# TEFNUT_proto_v1.net
KiCad netlist of a schematic drawn in EAGLE
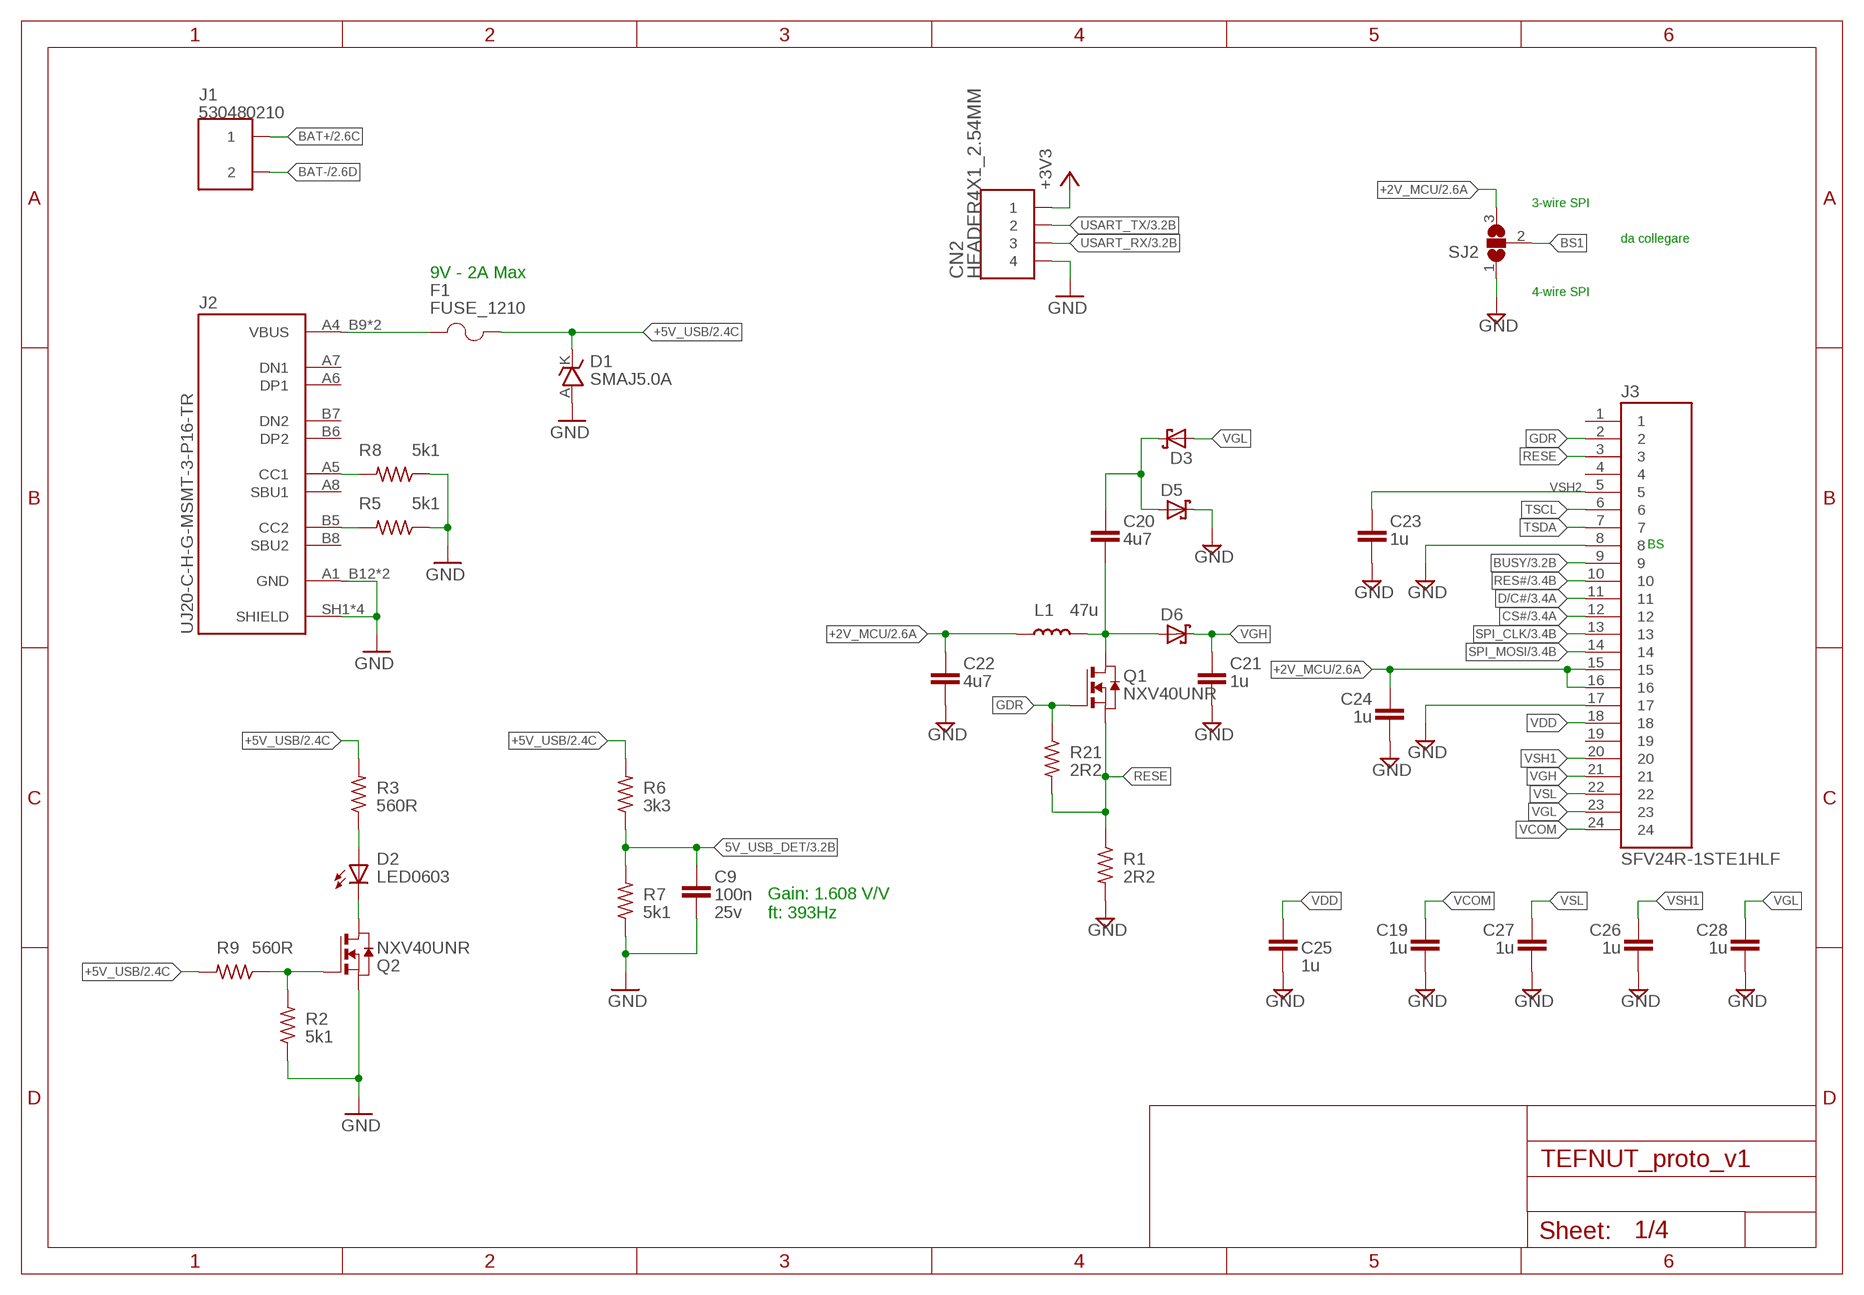
[diagram p0: schematic, sheet 1]
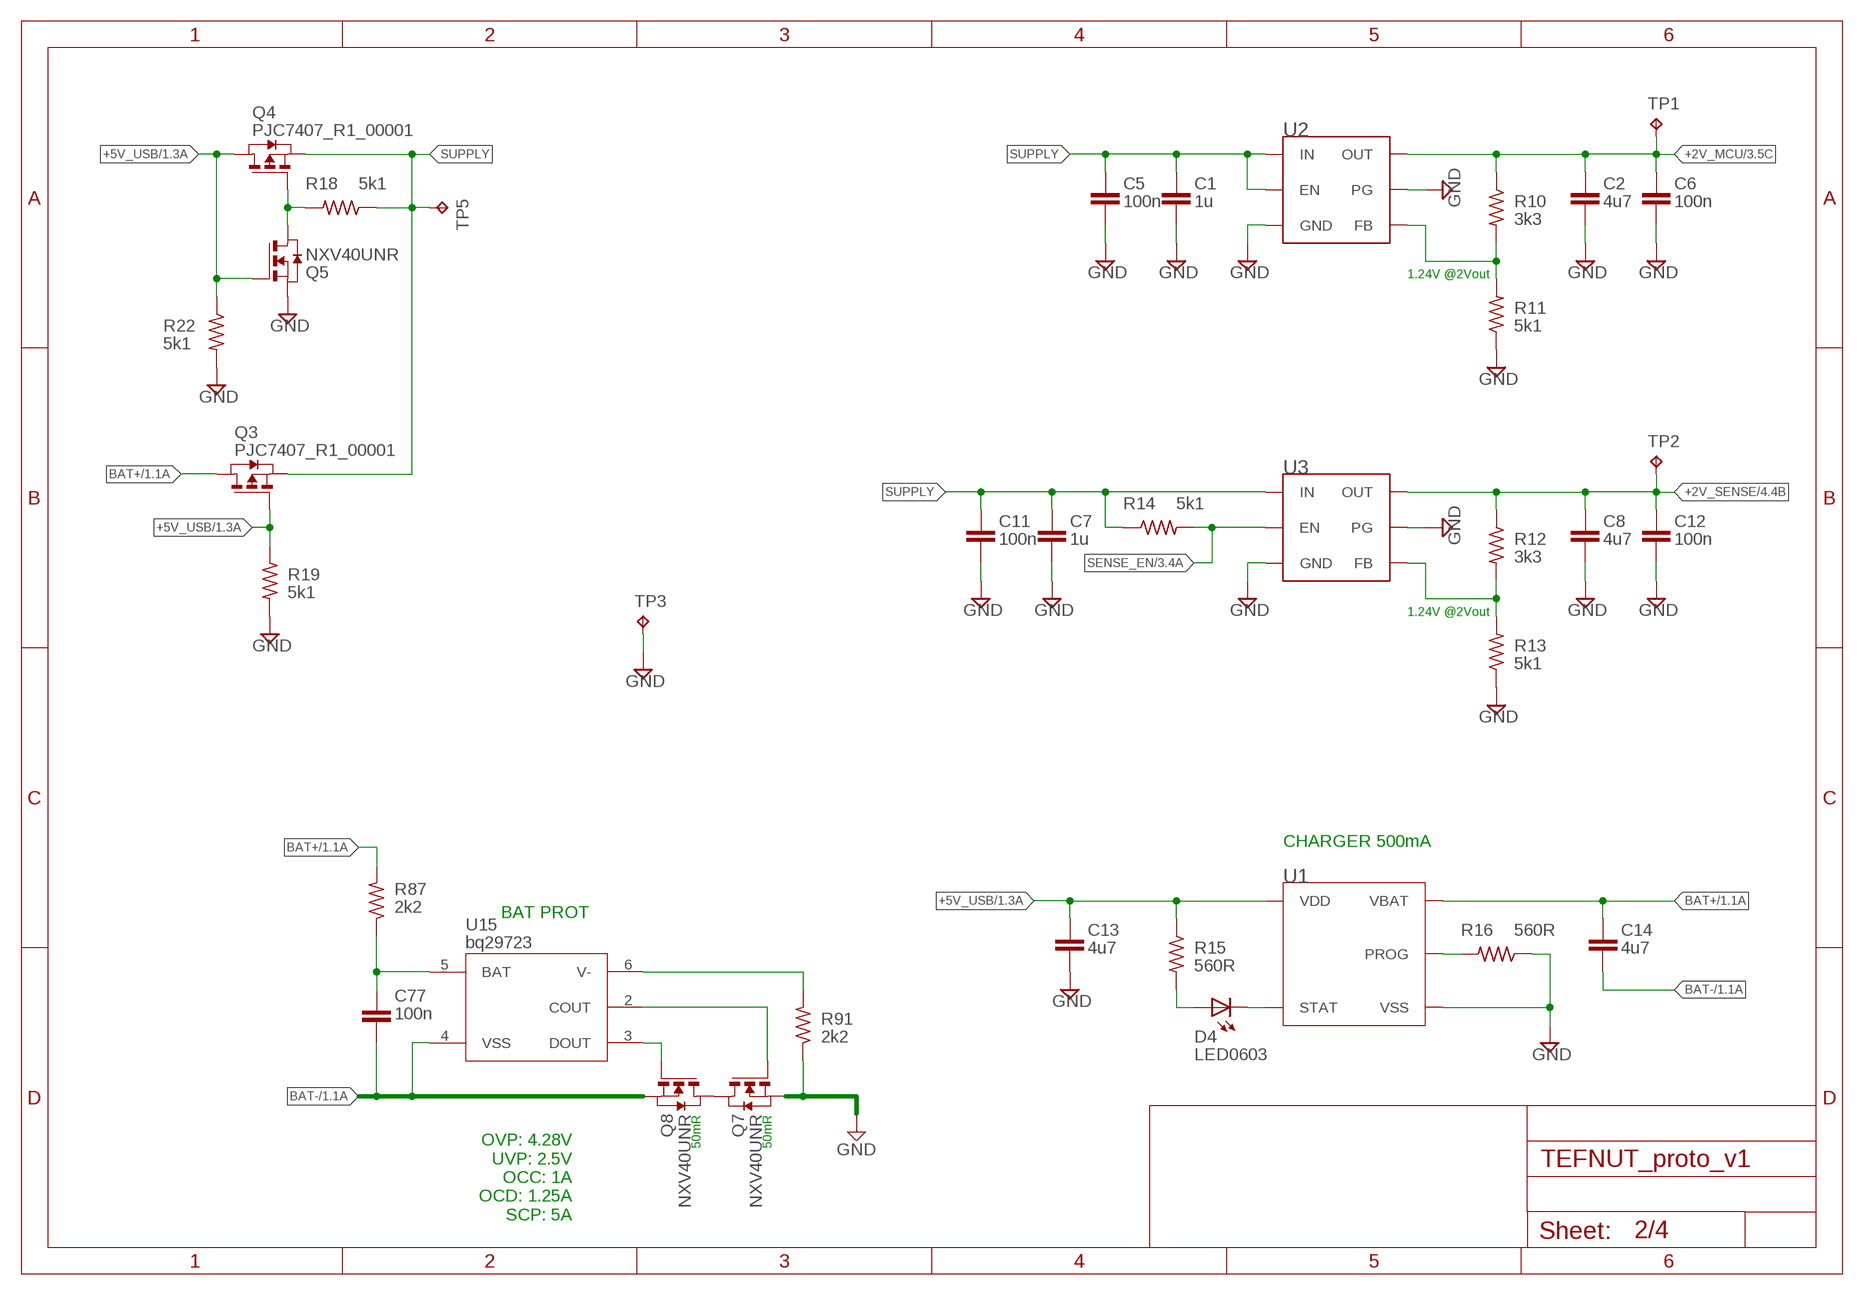
[diagram p1: schematic, sheet 2]
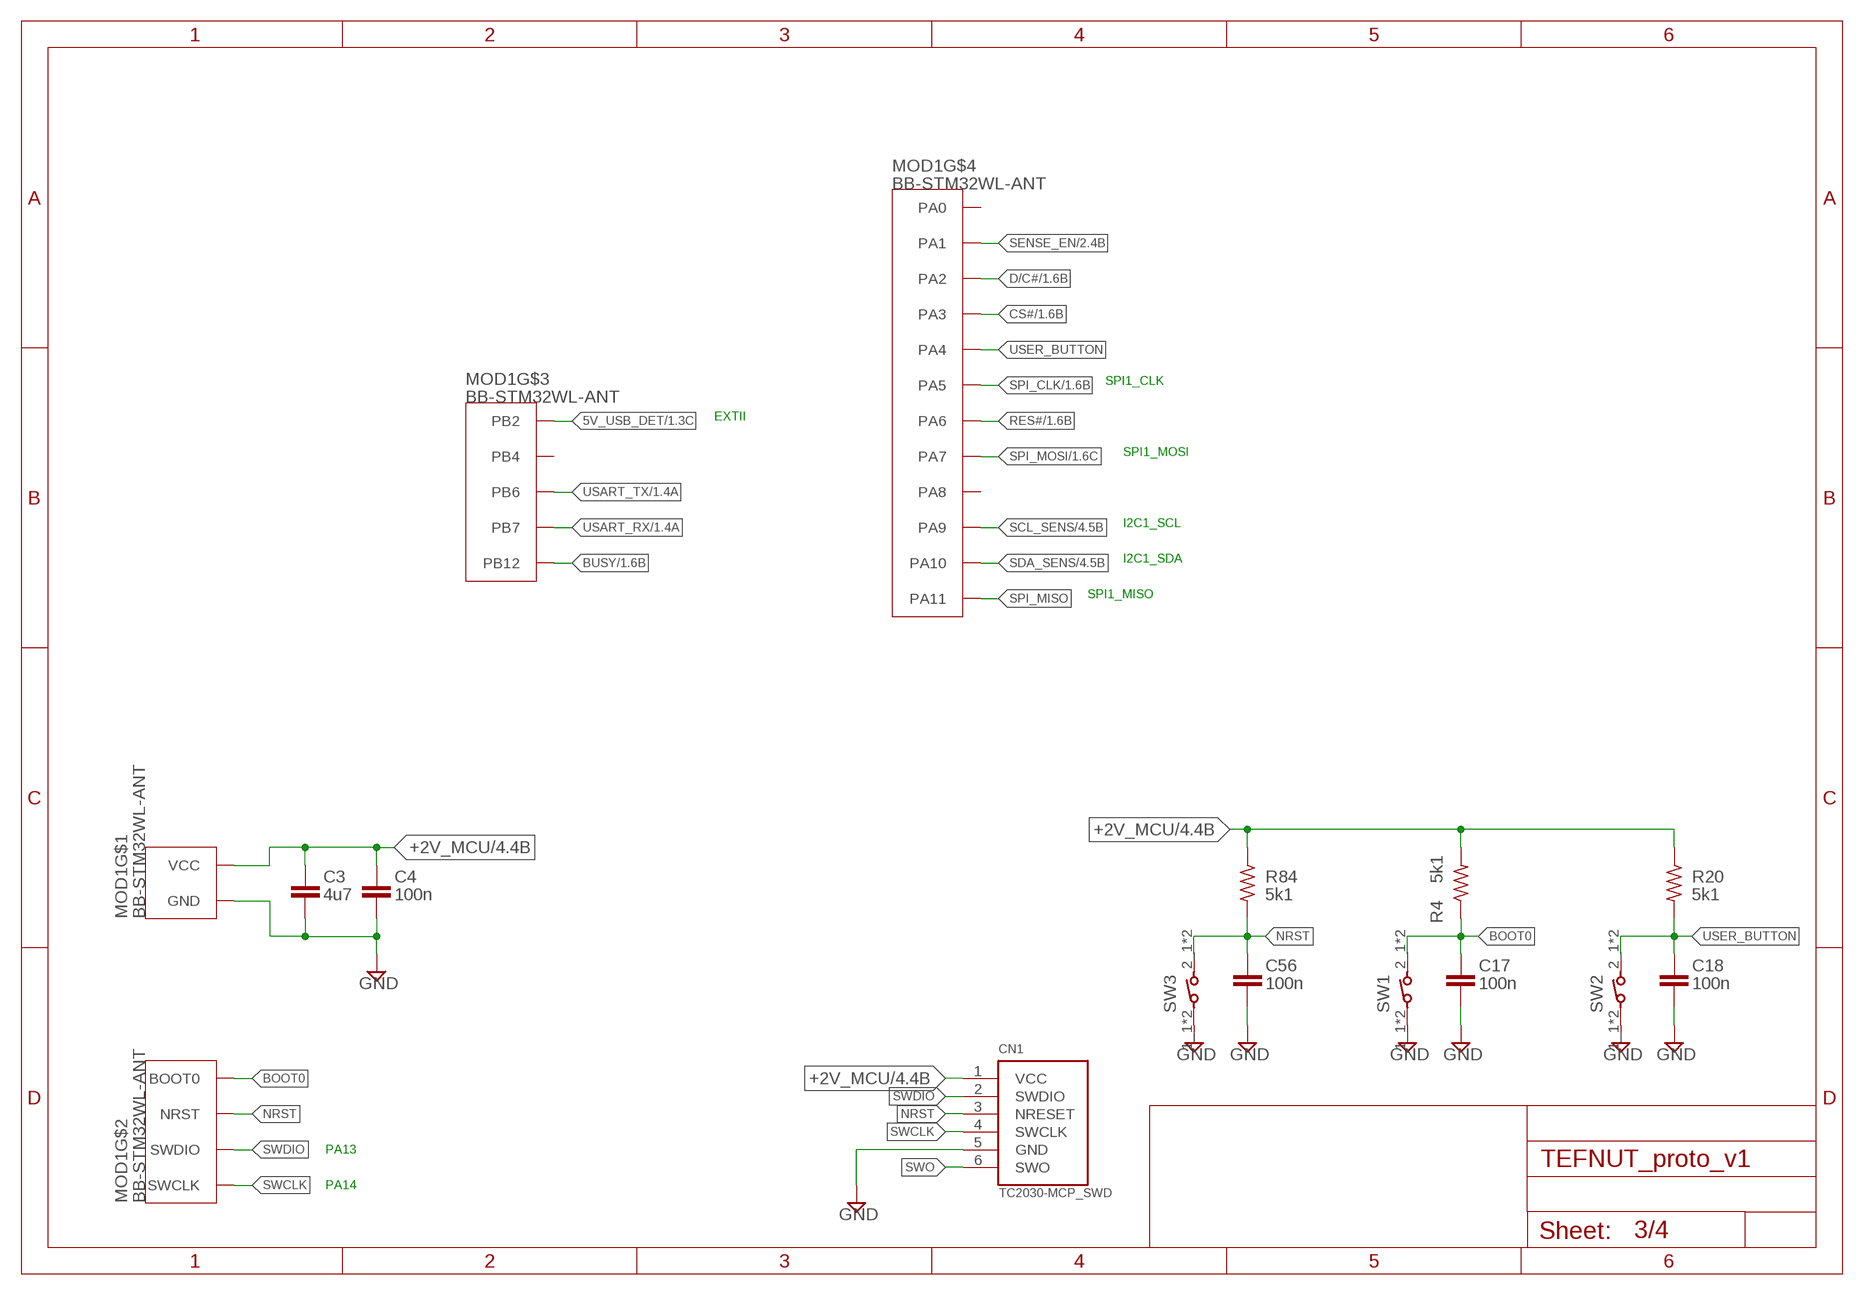
[diagram p2: schematic, sheet 3]
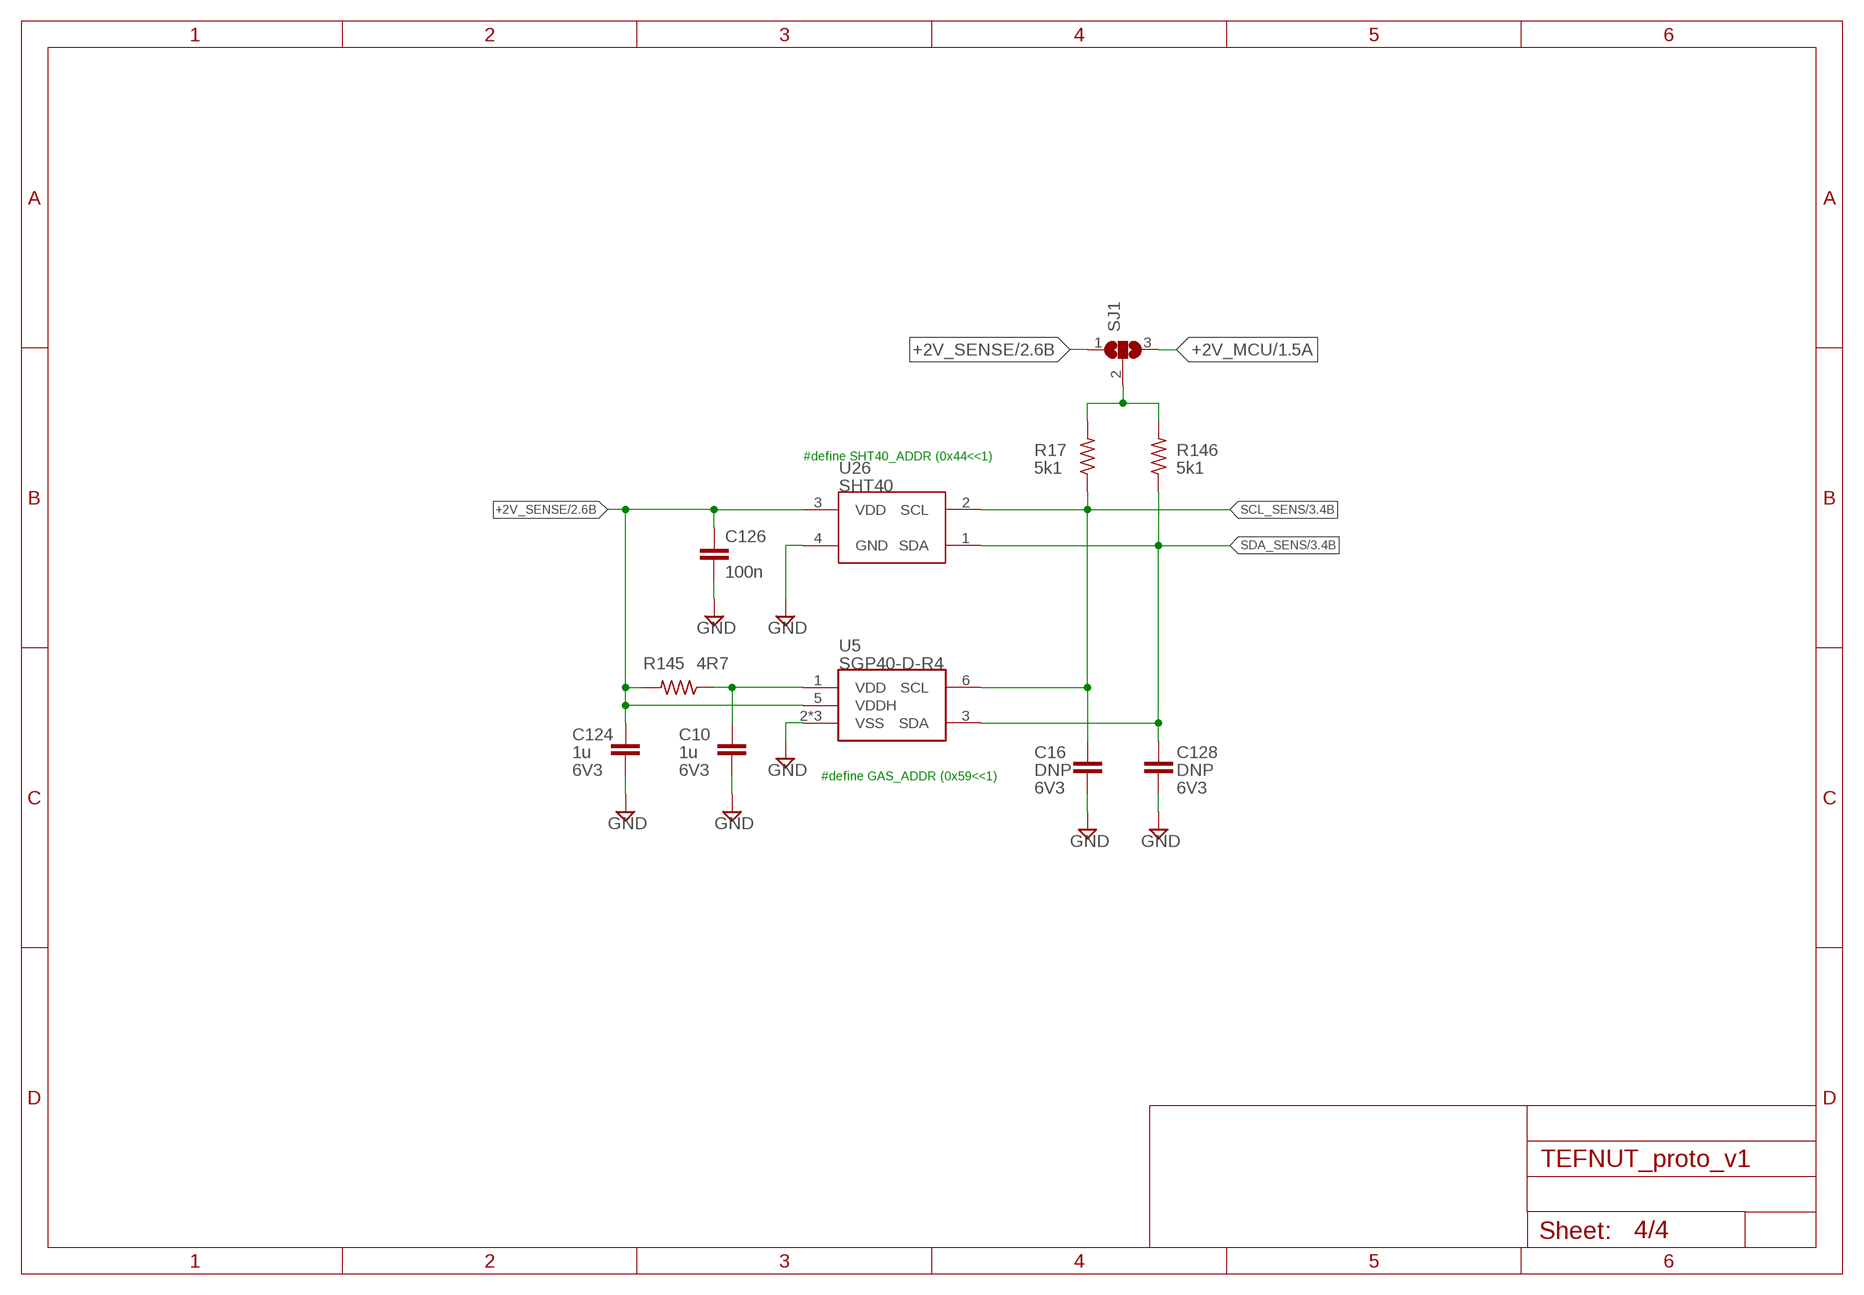
[diagram p3: schematic, sheet 4]

(export (version "E")
  (design (tool "Eeschema 10.0.6"))
  (components
    (comp (ref "C10")
      (value "1u")
      (footprint "eagle-import:C0603[1608]")
      (fields (field (name "PARTNO") "CL10A105KO8NNNC") (field (name "VOLT") "6V3"))
      (libsource (lib "eagle-import") (part "MP-PASS_vf.IZ1fKOIAQwecCdOCAm3Ehg_C0603"))
    )
    (comp (ref "C16")
      (value "DNP")
      (footprint "eagle-import:C0603[1608]")
      (fields (field (name "V") "6V3"))
      (libsource (lib "eagle-import") (part "C0603"))
    )
    (comp (ref "C124")
      (value "1u")
      (footprint "eagle-import:C0603[1608]")
      (fields (field (name "PARTNO") "CL10A105KO8NNNC") (field (name "VOLT") "6V3"))
      (libsource (lib "eagle-import") (part "MP-PASS_vf.IZ1fKOIAQwecCdOCAm3Ehg_C0603"))
    )
    (comp (ref "C126")
      (value "100n")
      (footprint "eagle-import:C0603[1608]")
      (fields (field (name "PARTNO") "CL10B104KO8NNNC"))
      (libsource (lib "eagle-import") (part "C0603"))
    )
    (comp (ref "C128")
      (value "DNP")
      (footprint "eagle-import:C0603[1608]")
      (fields (field (name "VOLT") "6V3"))
      (libsource (lib "eagle-import") (part "C0603"))
    )
    (comp (ref "R17")
      (value "5k1")
      (footprint "eagle-import:R0603[1608]")
      (fields (field (name "PARTNO") "RC0603FR-075K1L"))
      (libsource (lib "eagle-import") (part "R_0603"))
    )
    (comp (ref "R145")
      (value "4R7")
      (footprint "eagle-import:R0603")
      (fields (field (name "PARTNO") "AC0603FR-072R2L"))
      (libsource (lib "eagle-import") (part "MP-PASS_vf.IZ1fKOIAQwecCdOCAm3Ehg_R_0603"))
    )
    (comp (ref "R146")
      (value "5k1")
      (footprint "eagle-import:R0603[1608]")
      (fields (field (name "PARTNO") "RC0603FR-075K1L"))
      (libsource (lib "eagle-import") (part "R_0603"))
    )
    (comp (ref "SJ1")
      (value "SJ2W")
      (footprint "eagle-import:SJ_2")
      (libsource (lib "eagle-import") (part "SJ2W"))
    )
    (comp (ref "U5")
      (value "SGP40-D-R4")
      (footprint "eagle-import:DFN6")
      (fields (field (name "PARTNO") "SGP30-2.5K") (field (name "PARTNO_1") "SGP40-D-R4"))
      (libsource (lib "eagle-import") (part "SGP30"))
    )
    (comp (ref "U26")
      (value "SHT40")
      (footprint "eagle-import:SH4X")
      (fields (field (name "PARTNO") "SHT40-AD1B-R3"))
      (libsource (lib "eagle-import") (part "SHT40"))
    )
    (comp (ref "C3")
      (value "4u7")
      (footprint "eagle-import:C0805[2012]")
      (fields (field (name "PARTNO") "CL21A475KOFNNNE"))
      (libsource (lib "eagle-import") (part "MP-PASS_vf.IZ1fKOIAQwecCdOCAm3Ehg_C0805"))
    )
    (comp (ref "C4")
      (value "100n")
      (footprint "eagle-import:C0805[2012]")
      (fields (field (name "PARTNO") "CC0805KRX7R7BB104"))
      (libsource (lib "eagle-import") (part "MP-PASS_vf.IZ1fKOIAQwecCdOCAm3Ehg_C0805"))
    )
    (comp (ref "C17")
      (value "100n")
      (footprint "eagle-import:C0603[1608]")
      (fields (field (name "PARTNO") "CL10B104KO8NNNC"))
      (libsource (lib "eagle-import") (part "AlmaPASS_vf.OlGPyyHlR2mLU9oE-NbbHQ_C0603"))
    )
    (comp (ref "C18")
      (value "100n")
      (footprint "eagle-import:C0603[1608]")
      (fields (field (name "PARTNO") "CL10B104KO8NNNC"))
      (libsource (lib "eagle-import") (part "AlmaPASS_vf.OlGPyyHlR2mLU9oE-NbbHQ_C0603"))
    )
    (comp (ref "C56")
      (value "100n")
      (footprint "eagle-import:C0603[1608]")
      (fields (field (name "PARTNO") "CL10B104KO8NNNC"))
      (libsource (lib "eagle-import") (part "AlmaPASS_vf.OlGPyyHlR2mLU9oE-NbbHQ_C0603"))
    )
    (comp (ref "CN1")
      (value "TC2030-MCP_SWD")
      (footprint "eagle-import:TC2030-IDC")
      (libsource (lib "eagle-import") (part "TC2030-MCP_SWD"))
    )
    (comp (ref "MOD1")
      (value "BB-STM32WL-ANT")
      (footprint "eagle-import:BB-STM32WL-ANT")
      (libsource (lib "eagle-import") (part "BB-STM32WL-ANT"))
    )
    (comp (ref "R4")
      (value "5k1")
      (footprint "eagle-import:R0603")
      (fields (field (name "PARTNO") "RC0603FR-075K1L"))
      (libsource (lib "eagle-import") (part "MP-PASS_vf.IZ1fKOIAQwecCdOCAm3Ehg_R_0603"))
    )
    (comp (ref "R20")
      (value "5k1")
      (footprint "eagle-import:R0603")
      (fields (field (name "PARTNO") "RC0603FR-075K1L"))
      (libsource (lib "eagle-import") (part "MP-PASS_vf.IZ1fKOIAQwecCdOCAm3Ehg_R_0603"))
    )
    (comp (ref "R84")
      (value "5k1")
      (footprint "eagle-import:R0603")
      (fields (field (name "PARTNO") "RC0603FR-075K1L"))
      (libsource (lib "eagle-import") (part "MP-PASS_vf.IZ1fKOIAQwecCdOCAm3Ehg_R_0603"))
    )
    (comp (ref "SW1")
      (value "SWITCHEVQ_4PIN")
      (footprint "eagle-import:EVQ-P7L01P")
      (fields (field (name "PARTNO") "EVQP7L01P"))
      (libsource (lib "eagle-import") (part "SWITCHEVQ_4PIN"))
    )
    (comp (ref "SW2")
      (value "SWITCHEVQ_4PIN")
      (footprint "eagle-import:EVQ-P7L01P")
      (fields (field (name "PARTNO") "EVQP7L01P"))
      (libsource (lib "eagle-import") (part "SWITCHEVQ_4PIN"))
    )
    (comp (ref "SW3")
      (value "SWITCHEVQ_4PIN")
      (footprint "eagle-import:EVQ-P7L01P")
      (fields (field (name "PARTNO") "EVQP7L01P"))
      (libsource (lib "eagle-import") (part "SWITCHEVQ_4PIN"))
    )
    (comp (ref "C1")
      (value "1u")
      (footprint "eagle-import:C0603[1608]")
      (fields (field (name "PARTNO") "CL10A105KO8NNNC"))
      (libsource (lib "eagle-import") (part "MP-PASS_vf.IZ1fKOIAQwecCdOCAm3Ehg_C0603"))
    )
    (comp (ref "C2")
      (value "4u7")
      (footprint "eagle-import:C0603[1608]")
      (fields (field (name "PARTNO") "CL10A475KO8NNNC"))
      (libsource (lib "eagle-import") (part "MP-PASS_vf.IZ1fKOIAQwecCdOCAm3Ehg_C0603"))
    )
    (comp (ref "C5")
      (value "100n")
      (footprint "eagle-import:C0603[1608]")
      (fields (field (name "PARTNO") "CL10B104KO8NNNC"))
      (libsource (lib "eagle-import") (part "MP-PASS_vf.IZ1fKOIAQwecCdOCAm3Ehg_C0603"))
    )
    (comp (ref "C6")
      (value "100n")
      (footprint "eagle-import:C0603[1608]")
      (fields (field (name "PARTNO") "CL10B104KO8NNNC"))
      (libsource (lib "eagle-import") (part "MP-PASS_vf.IZ1fKOIAQwecCdOCAm3Ehg_C0603"))
    )
    (comp (ref "C7")
      (value "1u")
      (footprint "eagle-import:C0603[1608]")
      (fields (field (name "PARTNO") "CL10A105KO8NNNC"))
      (libsource (lib "eagle-import") (part "MP-PASS_vf.IZ1fKOIAQwecCdOCAm3Ehg_C0603"))
    )
    (comp (ref "C8")
      (value "4u7")
      (footprint "eagle-import:C0603[1608]")
      (fields (field (name "PARTNO") "CL10A475KO8NNNC"))
      (libsource (lib "eagle-import") (part "MP-PASS_vf.IZ1fKOIAQwecCdOCAm3Ehg_C0603"))
    )
    (comp (ref "C11")
      (value "100n")
      (footprint "eagle-import:C0603[1608]")
      (fields (field (name "PARTNO") "CL10B104KO8NNNC"))
      (libsource (lib "eagle-import") (part "MP-PASS_vf.IZ1fKOIAQwecCdOCAm3Ehg_C0603"))
    )
    (comp (ref "C12")
      (value "100n")
      (footprint "eagle-import:C0603[1608]")
      (fields (field (name "PARTNO") "CL10B104KO8NNNC"))
      (libsource (lib "eagle-import") (part "MP-PASS_vf.IZ1fKOIAQwecCdOCAm3Ehg_C0603"))
    )
    (comp (ref "C13")
      (value "4u7")
      (footprint "eagle-import:C0805[2012]")
      (fields (field (name "PARTNO") "CL21A475KOFNNNE"))
      (libsource (lib "eagle-import") (part "MP-PASS_vf.IZ1fKOIAQwecCdOCAm3Ehg_C0805"))
    )
    (comp (ref "C14")
      (value "4u7")
      (footprint "eagle-import:C0805[2012]")
      (fields (field (name "PARTNO") "CL21A475KOFNNNE"))
      (libsource (lib "eagle-import") (part "MP-PASS_vf.IZ1fKOIAQwecCdOCAm3Ehg_C0805"))
    )
    (comp (ref "C77")
      (value "100n")
      (footprint "eagle-import:C0603[1608]")
      (fields (field (name "PARTNO") "CL10B104KO8NNNC"))
      (libsource (lib "eagle-import") (part "MP-PASS_vf.IZ1fKOIAQwecCdOCAm3Ehg_C0603"))
    )
    (comp (ref "D4")
      (value "LED0603")
      (footprint "eagle-import:LED0603")
      (libsource (lib "eagle-import") (part "LED0603"))
    )
    (comp (ref "Q3")
      (value "PJC7407_R1_00001")
      (footprint "eagle-import:SOT323-3(SC-70-3)")
      (libsource (lib "eagle-import") (part "MOSFET_P_SOT323"))
    )
    (comp (ref "Q4")
      (value "PJC7407_R1_00001")
      (footprint "eagle-import:SOT323-3(SC-70-3)")
      (libsource (lib "eagle-import") (part "MOSFET_P_SOT323"))
    )
    (comp (ref "Q5")
      (value "NXV40UNR")
      (footprint "eagle-import:SOT23-3")
      (libsource (lib "eagle-import") (part "MOSFET_N_SOT23-3"))
    )
    (comp (ref "Q7")
      (value "NXV40UNR")
      (footprint "eagle-import:SOT23-3")
      (libsource (lib "eagle-import") (part "MOSFET_N_SOT23-3"))
    )
    (comp (ref "Q8")
      (value "NXV40UNR")
      (footprint "eagle-import:SOT23-3")
      (libsource (lib "eagle-import") (part "MOSFET_N_SOT23-3"))
    )
    (comp (ref "R10")
      (value "3k3")
      (footprint "eagle-import:R0603")
      (fields (field (name "PARTNO") "RC0603FR-073K3L"))
      (libsource (lib "eagle-import") (part "MP-PASS_vf.IZ1fKOIAQwecCdOCAm3Ehg_R_0603"))
    )
    (comp (ref "R11")
      (value "5k1")
      (footprint "eagle-import:R0603")
      (fields (field (name "PARTNO") "RC0603FR-075K1L"))
      (libsource (lib "eagle-import") (part "MP-PASS_vf.IZ1fKOIAQwecCdOCAm3Ehg_R_0603"))
    )
    (comp (ref "R12")
      (value "3k3")
      (footprint "eagle-import:R0603")
      (fields (field (name "PARTNO") "RC0603FR-073K3L"))
      (libsource (lib "eagle-import") (part "MP-PASS_vf.IZ1fKOIAQwecCdOCAm3Ehg_R_0603"))
    )
    (comp (ref "R13")
      (value "5k1")
      (footprint "eagle-import:R0603")
      (fields (field (name "PARTNO") "RC0603FR-075K1L"))
      (libsource (lib "eagle-import") (part "MP-PASS_vf.IZ1fKOIAQwecCdOCAm3Ehg_R_0603"))
    )
    (comp (ref "R14")
      (value "5k1")
      (footprint "eagle-import:R0603")
      (fields (field (name "PARTNO") "RC0603FR-075K1L"))
      (libsource (lib "eagle-import") (part "MP-PASS_vf.IZ1fKOIAQwecCdOCAm3Ehg_R_0603"))
    )
    (comp (ref "R15")
      (value "560R")
      (footprint "eagle-import:R0603")
      (fields (field (name "PARTNO") "RC0603FR-07560RL"))
      (libsource (lib "eagle-import") (part "MP-PASS_vf.IZ1fKOIAQwecCdOCAm3Ehg_R_0603"))
    )
    (comp (ref "R16")
      (value "560R")
      (footprint "eagle-import:R0603")
      (fields (field (name "PARTNO") "RC0603FR-07560RL"))
      (libsource (lib "eagle-import") (part "MP-PASS_vf.IZ1fKOIAQwecCdOCAm3Ehg_R_0603"))
    )
    (comp (ref "R18")
      (value "5k1")
      (footprint "eagle-import:R0603[1608]")
      (fields (field (name "PARTNO") "RC0603FR-075K1L"))
      (libsource (lib "eagle-import") (part "R_0603"))
    )
    (comp (ref "R19")
      (value "5k1")
      (footprint "eagle-import:R0603[1608]")
      (fields (field (name "PARTNO") "RC0603FR-075K1L"))
      (libsource (lib "eagle-import") (part "R_0603"))
    )
    (comp (ref "R22")
      (value "5k1")
      (footprint "eagle-import:R0603[1608]")
      (fields (field (name "PARTNO") "RC0603FR-075K1L"))
      (libsource (lib "eagle-import") (part "R_0603"))
    )
    (comp (ref "R87")
      (value "2k2")
      (footprint "eagle-import:R0603")
      (fields (field (name "PARTNO") "ERJ-3EKF2201V"))
      (libsource (lib "eagle-import") (part "MP-PASS_vf.IZ1fKOIAQwecCdOCAm3Ehg_R_0603"))
    )
    (comp (ref "R91")
      (value "2k2")
      (footprint "eagle-import:R0603")
      (fields (field (name "PARTNO") "ERJ-3EKF2201V"))
      (libsource (lib "eagle-import") (part "MP-PASS_vf.IZ1fKOIAQwecCdOCAm3Ehg_R_0603"))
    )
    (comp (ref "TP1")
      (value "TPB1,27")
      (footprint "eagle-import:B1,27")
      (libsource (lib "eagle-import") (part "TPB1,27"))
    )
    (comp (ref "TP2")
      (value "TPB1,27")
      (footprint "eagle-import:B1,27")
      (libsource (lib "eagle-import") (part "TPB1,27"))
    )
    (comp (ref "TP3")
      (value "TPB1,27")
      (footprint "eagle-import:B1,27")
      (libsource (lib "eagle-import") (part "TPB1,27"))
    )
    (comp (ref "TP5")
      (value "TPB1,27")
      (footprint "eagle-import:B1,27")
      (libsource (lib "eagle-import") (part "TPB1,27"))
    )
    (comp (ref "U1")
      (value "MCP73831T")
      (footprint "eagle-import:SOT23-5")
      (fields (field (name "PARTNO") "MCP73831T-2DCI/OT"))
      (libsource (lib "eagle-import") (part "MCP73831T"))
    )
    (comp (ref "U2")
      (value "TPS7A2501DRVRDRV0006A-IPC_B")
      (footprint "eagle-import:6-WDFN")
      (fields
        (field (name "MANUFACTURER_PART_NUMBER") "TPS7A2501DRVR")
        (field (name "COPYRIGHT") "Copyright (C) 2025 Ultra Librarian. All rights reserved.")
      )
      (libsource (lib "eagle-import") (part "TPS7A2501DRVRDRV0006A-IPC_B"))
    )
    (comp (ref "U3")
      (value "TPS7A2501DRVRDRV0006A-IPC_B")
      (footprint "eagle-import:6-WDFN")
      (fields
        (field (name "MANUFACTURER_PART_NUMBER") "TPS7A2501DRVR")
        (field (name "COPYRIGHT") "Copyright (C) 2025 Ultra Librarian. All rights reserved.")
      )
      (libsource (lib "eagle-import") (part "TPS7A2501DRVRDRV0006A-IPC_B"))
    )
    (comp (ref "U15")
      (value "bq29723")
      (footprint "eagle-import:WSON6")
      (fields (field (name "PARTNO") "BQ29704DSER"))
      (libsource (lib "eagle-import") (part "BQ297XX"))
    )
    (comp (ref "C9")
      (value "100n")
      (footprint "eagle-import:C0603[1608]")
      (fields (field (name "PARTNO") "CL10B104KO8NNNC") (field (name "VOLT") "25v"))
      (libsource (lib "eagle-import") (part "MP-PASS_vf.IZ1fKOIAQwecCdOCAm3Ehg_C0603"))
    )
    (comp (ref "C19")
      (value "1u")
      (footprint "eagle-import:C0603[1608]")
      (fields (field (name "PARTNO") "CL10A105KO8NNNC"))
      (libsource (lib "eagle-import") (part "MP-PASS_vf.IZ1fKOIAQwecCdOCAm3Ehg_C0603"))
    )
    (comp (ref "C20")
      (value "4u7")
      (footprint "eagle-import:C0603[1608]")
      (fields (field (name "PARTNO") "CL10A475KO8NNNC"))
      (libsource (lib "eagle-import") (part "MP-PASS_vf.IZ1fKOIAQwecCdOCAm3Ehg_C0603"))
    )
    (comp (ref "C21")
      (value "1u")
      (footprint "eagle-import:C0603[1608]")
      (fields (field (name "PARTNO") "CL10A105KO8NNNC"))
      (libsource (lib "eagle-import") (part "MP-PASS_vf.IZ1fKOIAQwecCdOCAm3Ehg_C0603"))
    )
    (comp (ref "C22")
      (value "4u7")
      (footprint "eagle-import:C0603[1608]")
      (fields (field (name "PARTNO") "CL10A475KO8NNNC"))
      (libsource (lib "eagle-import") (part "MP-PASS_vf.IZ1fKOIAQwecCdOCAm3Ehg_C0603"))
    )
    (comp (ref "C23")
      (value "1u")
      (footprint "eagle-import:C0603[1608]")
      (fields (field (name "PARTNO") "CL10A105KO8NNNC"))
      (libsource (lib "eagle-import") (part "MP-PASS_vf.IZ1fKOIAQwecCdOCAm3Ehg_C0603"))
    )
    (comp (ref "C24")
      (value "1u")
      (footprint "eagle-import:C0603[1608]")
      (fields (field (name "PARTNO") "CL10A105KO8NNNC"))
      (libsource (lib "eagle-import") (part "MP-PASS_vf.IZ1fKOIAQwecCdOCAm3Ehg_C0603"))
    )
    (comp (ref "C25")
      (value "1u")
      (footprint "eagle-import:C0603[1608]")
      (fields (field (name "PARTNO") "CL10A105KO8NNNC"))
      (libsource (lib "eagle-import") (part "MP-PASS_vf.IZ1fKOIAQwecCdOCAm3Ehg_C0603"))
    )
    (comp (ref "C26")
      (value "1u")
      (footprint "eagle-import:C0603[1608]")
      (fields (field (name "PARTNO") "CL10A105KO8NNNC"))
      (libsource (lib "eagle-import") (part "MP-PASS_vf.IZ1fKOIAQwecCdOCAm3Ehg_C0603"))
    )
    (comp (ref "C27")
      (value "1u")
      (footprint "eagle-import:C0603[1608]")
      (fields (field (name "PARTNO") "CL10A105KO8NNNC"))
      (libsource (lib "eagle-import") (part "MP-PASS_vf.IZ1fKOIAQwecCdOCAm3Ehg_C0603"))
    )
    (comp (ref "C28")
      (value "1u")
      (footprint "eagle-import:C0603[1608]")
      (fields (field (name "PARTNO") "CL10A105KO8NNNC"))
      (libsource (lib "eagle-import") (part "MP-PASS_vf.IZ1fKOIAQwecCdOCAm3Ehg_C0603"))
    )
    (comp (ref "CN2")
      (value "HEADER4X1_2.54MM")
      (footprint "eagle-import:HEADER4X1_2.54MM")
      (libsource (lib "eagle-import") (part "HEADER4X1_2.54MM"))
    )
    (comp (ref "D1")
      (value "TVS214AC")
      (footprint "eagle-import:DO-214AC")
      (fields (field (name "PARTNO") "SMAJ5.0A"))
      (libsource (lib "eagle-import") (part "TVS214AC"))
    )
    (comp (ref "D2")
      (value "LED0603")
      (footprint "eagle-import:LED0603")
      (libsource (lib "eagle-import") (part "LED0603"))
    )
    (comp (ref "D3")
      (value "SCHOTTKY_DIODE_SOD123")
      (footprint "eagle-import:SOD123")
      (fields (field (name "PARTNO") "MBR0530"))
      (libsource (lib "eagle-import") (part "SCHOTTKY_DIODE_SOD123"))
    )
    (comp (ref "D5")
      (value "SCHOTTKY_DIODE_SOD123")
      (footprint "eagle-import:SOD123")
      (fields (field (name "PARTNO") "MBR0530"))
      (libsource (lib "eagle-import") (part "SCHOTTKY_DIODE_SOD123"))
    )
    (comp (ref "D6")
      (value "SCHOTTKY_DIODE_SOD123")
      (footprint "eagle-import:SOD123")
      (fields (field (name "PARTNO") "MBR0530"))
      (libsource (lib "eagle-import") (part "SCHOTTKY_DIODE_SOD123"))
    )
    (comp (ref "F1")
      (value "FUSE_1210")
      (footprint "eagle-import:R1210[3225]")
      (fields (field (name "PARTNO") "SMD1210B110TF/16"))
      (libsource (lib "eagle-import") (part "FUSE_1210"))
    )
    (comp (ref "J1")
      (value "530480210")
      (footprint "eagle-import:530480210")
      (libsource (lib "eagle-import") (part "530480210"))
    )
    (comp (ref "J2")
      (value "UJ20-C-H-G-MSMT-3-P16-TR")
      (footprint "eagle-import:SAMESKY_UJ20-C-H-G-MSMT-3-P16-TR")
      (fields (field (name "MANUFACTURER") "Same Sky") (field (name "PARTNO") "UJ20-C-H-G-MSMT-3-P16"))
      (libsource (lib "eagle-import") (part "UJ20-C-H-G-MSMT-3-P16-TR"))
    )
    (comp (ref "J3")
      (value "SFV24R-1STE1HLF")
      (footprint "eagle-import:AMPHENOL_SFV24R-1STE1HLF")
      (fields (field (name "MANUFACTURER") "Amphenol"))
      (libsource (lib "eagle-import") (part "SFV24R-1STE1HLF"))
    )
    (comp (ref "L1")
      (value "47u")
      (footprint "eagle-import:L0805[2012]")
      (fields (field (name "PARTNO") "MLF2012E100JT000"))
      (libsource (lib "eagle-import") (part "L0805"))
    )
    (comp (ref "Q1")
      (value "NXV40UNR")
      (footprint "eagle-import:SOT23-3")
      (libsource (lib "eagle-import") (part "MOSFET_N_SOT23-3"))
    )
    (comp (ref "Q2")
      (value "NXV40UNR")
      (footprint "eagle-import:SOT23-3")
      (libsource (lib "eagle-import") (part "MOSFET_N_SOT23-3"))
    )
    (comp (ref "R1")
      (value "2R2")
      (footprint "eagle-import:R0603")
      (fields (field (name "PARTNO") "ERJ-U03F2R20V"))
      (libsource (lib "eagle-import") (part "MP-PASS_vf.IZ1fKOIAQwecCdOCAm3Ehg_R_0603"))
    )
    (comp (ref "R2")
      (value "5k1")
      (footprint "eagle-import:R0603")
      (fields (field (name "PARTNO") "RC0603FR-075K1L"))
      (libsource (lib "eagle-import") (part "MP-PASS_vf.IZ1fKOIAQwecCdOCAm3Ehg_R_0603"))
    )
    (comp (ref "R3")
      (value "560R")
      (footprint "eagle-import:R0603")
      (fields (field (name "PARTNO") "RC0603FR-07560RL"))
      (libsource (lib "eagle-import") (part "MP-PASS_vf.IZ1fKOIAQwecCdOCAm3Ehg_R_0603"))
    )
    (comp (ref "R5")
      (value "5k1")
      (footprint "eagle-import:R0603")
      (fields (field (name "PARTNO") "RC0603FR-075K1L"))
      (libsource (lib "eagle-import") (part "MP-PASS_vf.IZ1fKOIAQwecCdOCAm3Ehg_R_0603"))
    )
    (comp (ref "R6")
      (value "3k3")
      (footprint "eagle-import:R0603")
      (fields (field (name "PARTNO") "RC0603FR-073K3L"))
      (libsource (lib "eagle-import") (part "MP-PASS_vf.IZ1fKOIAQwecCdOCAm3Ehg_R_0603"))
    )
    (comp (ref "R7")
      (value "5k1")
      (footprint "eagle-import:R0603")
      (fields (field (name "PARTNO") "RC0603FR-075K1L"))
      (libsource (lib "eagle-import") (part "MP-PASS_vf.IZ1fKOIAQwecCdOCAm3Ehg_R_0603"))
    )
    (comp (ref "R8")
      (value "5k1")
      (footprint "eagle-import:R0603")
      (fields (field (name "PARTNO") "RC0603FR-075K1L"))
      (libsource (lib "eagle-import") (part "MP-PASS_vf.IZ1fKOIAQwecCdOCAm3Ehg_R_0603"))
    )
    (comp (ref "R9")
      (value "560R")
      (footprint "eagle-import:R0603")
      (fields (field (name "PARTNO") "RC0603FR-07560RL"))
      (libsource (lib "eagle-import") (part "MP-PASS_vf.IZ1fKOIAQwecCdOCAm3Ehg_R_0603"))
    )
    (comp (ref "R21")
      (value "2R2")
      (footprint "eagle-import:R0603")
      (fields (field (name "PARTNO") "ERJ-U03F2R20V"))
      (libsource (lib "eagle-import") (part "MP-PASS_vf.IZ1fKOIAQwecCdOCAm3Ehg_R_0603"))
    )
    (comp (ref "SJ2")
      (value "SJ2W")
      (footprint "eagle-import:SJ_2")
      (libsource (lib "eagle-import") (part "SJ2W"))
    )
  )
  (nets
    (net (code "1") (name "+2V_MCU") (class "Default")
      (node (ref "C2") (pin "1") (pinfunction "1_1") (pintype "passive"))
      (node (ref "C22") (pin "1") (pinfunction "1_1") (pintype "passive"))
      (node (ref "C24") (pin "1") (pinfunction "1_1") (pintype "passive"))
      (node (ref "C3") (pin "1") (pinfunction "1_1") (pintype "passive"))
      (node (ref "C4") (pin "1") (pinfunction "1_1") (pintype "passive"))
      (node (ref "C6") (pin "1") (pinfunction "1_1") (pintype "passive"))
      (node (ref "CN1") (pin "1") (pinfunction "VCC_1") (pintype "bidirectional"))
      (node (ref "J3") (pin "15") (pinfunction "15_15") (pintype "passive"))
      (node (ref "J3") (pin "16") (pinfunction "16_16") (pintype "passive"))
      (node (ref "L1") (pin "1") (pinfunction "1_1") (pintype "passive"))
      (node (ref "MOD1") (pin "VCC") (pinfunction "VCC_VCC") (pintype "bidirectional"))
      (node (ref "R10") (pin "1") (pinfunction "1_1") (pintype "passive"))
      (node (ref "R20") (pin "1") (pinfunction "1_1") (pintype "passive"))
      (node (ref "R4") (pin "2") (pinfunction "2_2") (pintype "passive"))
      (node (ref "R84") (pin "1") (pinfunction "1_1") (pintype "passive"))
      (node (ref "SJ1") (pin "3") (pinfunction "3_3") (pintype "passive"))
      (node (ref "SJ2") (pin "3") (pinfunction "3_3") (pintype "passive"))
      (node (ref "TP1") (pin "TP") (pinfunction "TP_TP") (pintype "input"))
      (node (ref "U2") (pin "1") (pinfunction "OUT_1") (pintype "power_in"))
    )
    (net (code "2") (name "+2V_SENSE") (class "Default")
      (node (ref "C12") (pin "1") (pinfunction "1_1") (pintype "passive"))
      (node (ref "C124") (pin "2") (pinfunction "2_2") (pintype "passive"))
      (node (ref "C126") (pin "1") (pinfunction "1_1") (pintype "passive"))
      (node (ref "C8") (pin "1") (pinfunction "1_1") (pintype "passive"))
      (node (ref "R12") (pin "1") (pinfunction "1_1") (pintype "passive"))
      (node (ref "R145") (pin "2") (pinfunction "2_2") (pintype "passive"))
      (node (ref "SJ1") (pin "1") (pinfunction "1_1") (pintype "passive"))
      (node (ref "TP2") (pin "TP") (pinfunction "TP_TP") (pintype "input"))
      (node (ref "U26") (pin "3") (pinfunction "VDD_3") (pintype "bidirectional"))
      (node (ref "U3") (pin "1") (pinfunction "OUT_1") (pintype "power_in"))
      (node (ref "U5") (pin "5") (pinfunction "VDDH_5") (pintype "bidirectional"))
    )
    (net (code "3") (name "+3V3") (class "Default")
      (node (ref "CN2") (pin "1") (pinfunction "1_1") (pintype "bidirectional"))
    )
    (net (code "4") (name "+5V_USB") (class "Default")
      (node (ref "C13") (pin "1") (pinfunction "1_1") (pintype "passive"))
      (node (ref "D1") (pin "K") (pinfunction "K_K") (pintype "bidirectional"))
      (node (ref "F1") (pin "2") (pinfunction "2_2") (pintype "bidirectional"))
      (node (ref "Q3") (pin "1") (pinfunction "G_1") (pintype "passive"))
      (node (ref "Q4") (pin "3") (pinfunction "D_3") (pintype "passive"))
      (node (ref "Q5") (pin "1") (pinfunction "G_1") (pintype "passive"))
      (node (ref "R15") (pin "1") (pinfunction "1_1") (pintype "passive"))
      (node (ref "R19") (pin "1") (pinfunction "1_1") (pintype "passive"))
      (node (ref "R22") (pin "1") (pinfunction "1_1") (pintype "passive"))
      (node (ref "R3") (pin "2") (pinfunction "2_2") (pintype "passive"))
      (node (ref "R6") (pin "2") (pinfunction "2_2") (pintype "passive"))
      (node (ref "R9") (pin "2") (pinfunction "2_2") (pintype "passive"))
      (node (ref "U1") (pin "4") (pinfunction "VDD_4") (pintype "passive"))
    )
    (net (code "5") (name "5V_USB_DET") (class "Default")
      (node (ref "C9") (pin "1") (pinfunction "1_1") (pintype "passive"))
      (node (ref "MOD1") (pin "PB2") (pinfunction "PB2_PB2") (pintype "bidirectional"))
      (node (ref "R6") (pin "1") (pinfunction "1_1") (pintype "passive"))
      (node (ref "R7") (pin "2") (pinfunction "2_2") (pintype "passive"))
    )
    (net (code "6") (name "BAT+") (class "Default")
      (node (ref "C14") (pin "1") (pinfunction "1_1") (pintype "passive"))
      (node (ref "J1") (pin "1") (pinfunction "1_1") (pintype "bidirectional"))
      (node (ref "Q3") (pin "3") (pinfunction "D_3") (pintype "passive"))
      (node (ref "R87") (pin "2") (pinfunction "2_2") (pintype "passive"))
      (node (ref "U1") (pin "3") (pinfunction "VBAT_3") (pintype "passive"))
    )
    (net (code "7") (name "BAT-") (class "Default")
      (node (ref "C14") (pin "2") (pinfunction "2_2") (pintype "passive"))
      (node (ref "C77") (pin "2") (pinfunction "2_2") (pintype "passive"))
      (node (ref "J1") (pin "2") (pinfunction "2_2") (pintype "bidirectional"))
      (node (ref "Q8") (pin "2") (pinfunction "S_2") (pintype "passive"))
      (node (ref "U15") (pin "4") (pinfunction "VSS_4") (pintype "bidirectional"))
    )
    (net (code "8") (name "BOOT0") (class "Default")
      (node (ref "C17") (pin "1") (pinfunction "1_1") (pintype "passive"))
      (node (ref "MOD1") (pin "BOOT0") (pinfunction "BOOT0_BOOT0") (pintype "bidirectional"))
      (node (ref "R4") (pin "1") (pinfunction "1_1") (pintype "passive"))
      (node (ref "SW1") (pin "2_1") (pinfunction "2_2_1") (pintype "passive"))
      (node (ref "SW1") (pin "2_2") (pinfunction "2_2_2") (pintype "passive"))
    )
    (net (code "9") (name "BS1") (class "Default")
      (node (ref "SJ2") (pin "2") (pinfunction "2_2") (pintype "passive"))
    )
    (net (code "10") (name "BUSY") (class "Default")
      (node (ref "J3") (pin "9") (pinfunction "9_9") (pintype "passive"))
      (node (ref "MOD1") (pin "PB12") (pinfunction "PB12_PB12") (pintype "bidirectional"))
    )
    (net (code "11") (name "CS#") (class "Default")
      (node (ref "J3") (pin "12") (pinfunction "12_12") (pintype "passive"))
      (node (ref "MOD1") (pin "PA3") (pinfunction "PA3_PA3") (pintype "bidirectional"))
    )
    (net (code "12") (name "D{slash}C#") (class "Default")
      (node (ref "J3") (pin "11") (pinfunction "11_11") (pintype "passive"))
      (node (ref "MOD1") (pin "PA2") (pinfunction "PA2_PA2") (pintype "bidirectional"))
    )
    (net (code "13") (name "GDR") (class "Default")
      (node (ref "J3") (pin "2") (pinfunction "2_2") (pintype "passive"))
      (node (ref "Q1") (pin "1") (pinfunction "G_1") (pintype "passive"))
      (node (ref "R21") (pin "1") (pinfunction "1_1") (pintype "passive"))
    )
    (net (code "14") (name "GND") (class "Default")
      (node (ref "C1") (pin "2") (pinfunction "2_2") (pintype "passive"))
      (node (ref "C10") (pin "1") (pinfunction "1_1") (pintype "passive"))
      (node (ref "C11") (pin "2") (pinfunction "2_2") (pintype "passive"))
      (node (ref "C12") (pin "2") (pinfunction "2_2") (pintype "passive"))
      (node (ref "C124") (pin "1") (pinfunction "1_1") (pintype "passive"))
      (node (ref "C126") (pin "2") (pinfunction "2_2") (pintype "passive"))
      (node (ref "C128") (pin "1") (pinfunction "1_1") (pintype "passive"))
      (node (ref "C13") (pin "2") (pinfunction "2_2") (pintype "passive"))
      (node (ref "C16") (pin "1") (pinfunction "1_1") (pintype "passive"))
      (node (ref "C17") (pin "2") (pinfunction "2_2") (pintype "passive"))
      (node (ref "C18") (pin "2") (pinfunction "2_2") (pintype "passive"))
      (node (ref "C19") (pin "2") (pinfunction "2_2") (pintype "passive"))
      (node (ref "C2") (pin "2") (pinfunction "2_2") (pintype "passive"))
      (node (ref "C21") (pin "2") (pinfunction "2_2") (pintype "passive"))
      (node (ref "C22") (pin "2") (pinfunction "2_2") (pintype "passive"))
      (node (ref "C23") (pin "2") (pinfunction "2_2") (pintype "passive"))
      (node (ref "C24") (pin "2") (pinfunction "2_2") (pintype "passive"))
      (node (ref "C25") (pin "2") (pinfunction "2_2") (pintype "passive"))
      (node (ref "C26") (pin "2") (pinfunction "2_2") (pintype "passive"))
      (node (ref "C27") (pin "2") (pinfunction "2_2") (pintype "passive"))
      (node (ref "C28") (pin "2") (pinfunction "2_2") (pintype "passive"))
      (node (ref "C3") (pin "2") (pinfunction "2_2") (pintype "passive"))
      (node (ref "C4") (pin "2") (pinfunction "2_2") (pintype "passive"))
      (node (ref "C5") (pin "2") (pinfunction "2_2") (pintype "passive"))
      (node (ref "C56") (pin "2") (pinfunction "2_2") (pintype "passive"))
      (node (ref "C6") (pin "2") (pinfunction "2_2") (pintype "passive"))
      (node (ref "C7") (pin "2") (pinfunction "2_2") (pintype "passive"))
      (node (ref "C8") (pin "2") (pinfunction "2_2") (pintype "passive"))
      (node (ref "C9") (pin "2") (pinfunction "2_2") (pintype "passive"))
      (node (ref "CN1") (pin "5") (pinfunction "GND_5") (pintype "bidirectional"))
      (node (ref "CN2") (pin "4") (pinfunction "4_4") (pintype "bidirectional"))
      (node (ref "D1") (pin "A") (pinfunction "A_A") (pintype "bidirectional"))
      (node (ref "D5") (pin "K") (pinfunction "K_K") (pintype "passive"))
      (node (ref "J2") (pin "A1_B12") (pinfunction "GND_A1_B12") (pintype "power_in"))
      (node (ref "J2") (pin "B1_A12") (pinfunction "GND_B1_A12") (pintype "power_in"))
      (node (ref "J2") (pin "SH1") (pinfunction "SHIELD_SH1") (pintype "passive"))
      (node (ref "J2") (pin "SH2") (pinfunction "SHIELD_SH2") (pintype "passive"))
      (node (ref "J2") (pin "SH3") (pinfunction "SHIELD_SH3") (pintype "passive"))
      (node (ref "J2") (pin "SH4") (pinfunction "SHIELD_SH4") (pintype "passive"))
      (node (ref "J3") (pin "17") (pinfunction "17_17") (pintype "passive"))
      (node (ref "J3") (pin "8") (pinfunction "8_8") (pintype "passive"))
      (node (ref "MOD1") (pin "GND") (pinfunction "GND_GND") (pintype "bidirectional"))
      (node (ref "MOD1") (pin "GND@2") (pinfunction "GND_GND@2") (pintype "bidirectional"))
      (node (ref "Q2") (pin "2") (pinfunction "S_2") (pintype "passive"))
      (node (ref "Q5") (pin "2") (pinfunction "S_2") (pintype "passive"))
      (node (ref "Q7") (pin "2") (pinfunction "S_2") (pintype "passive"))
      (node (ref "R1") (pin "2") (pinfunction "2_2") (pintype "passive"))
      (node (ref "R11") (pin "1") (pinfunction "1_1") (pintype "passive"))
      (node (ref "R13") (pin "1") (pinfunction "1_1") (pintype "passive"))
      (node (ref "R16") (pin "1") (pinfunction "1_1") (pintype "passive"))
      (node (ref "R19") (pin "2") (pinfunction "2_2") (pintype "passive"))
      (node (ref "R2") (pin "1") (pinfunction "1_1") (pintype "passive"))
      (node (ref "R22") (pin "2") (pinfunction "2_2") (pintype "passive"))
      (node (ref "R5") (pin "1") (pinfunction "1_1") (pintype "passive"))
      (node (ref "R7") (pin "1") (pinfunction "1_1") (pintype "passive"))
      (node (ref "R8") (pin "1") (pinfunction "1_1") (pintype "passive"))
      (node (ref "R91") (pin "1") (pinfunction "1_1") (pintype "passive"))
      (node (ref "SJ2") (pin "1") (pinfunction "1_1") (pintype "passive"))
      (node (ref "SW1") (pin "1_1") (pinfunction "1_1_1") (pintype "passive"))
      (node (ref "SW1") (pin "1_2") (pinfunction "1_1_2") (pintype "passive"))
      (node (ref "SW2") (pin "1_1") (pinfunction "1_1_1") (pintype "passive"))
      (node (ref "SW2") (pin "1_2") (pinfunction "1_1_2") (pintype "passive"))
      (node (ref "SW3") (pin "1_1") (pinfunction "1_1_1") (pintype "passive"))
      (node (ref "SW3") (pin "1_2") (pinfunction "1_1_2") (pintype "passive"))
      (node (ref "TP3") (pin "TP") (pinfunction "TP_TP") (pintype "input"))
      (node (ref "U1") (pin "2") (pinfunction "VSS_2") (pintype "passive"))
      (node (ref "U2") (pin "3") (pinfunction "PG_3") (pintype "open_collector"))
      (node (ref "U2") (pin "5") (pinfunction "GND_5") (pintype "power_in"))
      (node (ref "U2") (pin "7") (pinfunction "GND_7") (pintype "power_in"))
      (node (ref "U26") (pin "4") (pinfunction "GND_4") (pintype "bidirectional"))
      (node (ref "U3") (pin "3") (pinfunction "PG_3") (pintype "open_collector"))
      (node (ref "U3") (pin "5") (pinfunction "GND_5") (pintype "power_in"))
      (node (ref "U3") (pin "7") (pinfunction "GND_7") (pintype "power_in"))
      (node (ref "U5") (pin "2") (pinfunction "VSS_2") (pintype "bidirectional"))
      (node (ref "U5") (pin "4") (pinfunction "VSS_4") (pintype "bidirectional"))
      (node (ref "U5") (pin "7") (pinfunction "VSS_7") (pintype "bidirectional"))
    )
    (net (code "15") (name "NRST") (class "Default")
      (node (ref "C56") (pin "1") (pinfunction "1_1") (pintype "passive"))
      (node (ref "CN1") (pin "3") (pinfunction "NRESET_3") (pintype "bidirectional"))
      (node (ref "MOD1") (pin "NRST") (pinfunction "NRST_NRST") (pintype "bidirectional"))
      (node (ref "R84") (pin "2") (pinfunction "2_2") (pintype "passive"))
      (node (ref "SW3") (pin "2_1") (pinfunction "2_2_1") (pintype "passive"))
      (node (ref "SW3") (pin "2_2") (pinfunction "2_2_2") (pintype "passive"))
    )
    (net (code "16") (name "Net-(C20-Pad1)") (class "Default")
      (node (ref "C20") (pin "1") (pinfunction "1_1") (pintype "passive"))
      (node (ref "D3") (pin "K") (pinfunction "K_K") (pintype "passive"))
      (node (ref "D5") (pin "A") (pinfunction "A_A") (pintype "passive"))
    )
    (net (code "17") (name "Net-(D2-A)") (class "Default")
      (node (ref "D2") (pin "1") (pinfunction "A_1") (pintype "passive"))
      (node (ref "R3") (pin "1") (pinfunction "1_1") (pintype "passive"))
    )
    (net (code "18") (name "Net-(D2-K)") (class "Default")
      (node (ref "D2") (pin "2") (pinfunction "K_2") (pintype "passive"))
      (node (ref "Q2") (pin "3") (pinfunction "D_3") (pintype "passive"))
    )
    (net (code "19") (name "Net-(D4-A)") (class "Default")
      (node (ref "D4") (pin "1") (pinfunction "A_1") (pintype "passive"))
      (node (ref "R15") (pin "2") (pinfunction "2_2") (pintype "passive"))
    )
    (net (code "20") (name "Net-(D4-K)") (class "Default")
      (node (ref "D4") (pin "2") (pinfunction "K_2") (pintype "passive"))
      (node (ref "U1") (pin "1") (pinfunction "STAT_1") (pintype "passive"))
    )
    (net (code "21") (name "Net-(F1-Pad1)") (class "Default")
      (node (ref "F1") (pin "1") (pinfunction "1_1") (pintype "bidirectional"))
      (node (ref "J2") (pin "A4_B9") (pinfunction "VBUS_A4_B9") (pintype "power_in"))
      (node (ref "J2") (pin "B4_A9") (pinfunction "VBUS_B4_A9") (pintype "power_in"))
    )
    (net (code "22") (name "Net-(J2-CC1)") (class "Default")
      (node (ref "J2") (pin "A5") (pinfunction "CC1_A5") (pintype "passive"))
      (node (ref "R8") (pin "2") (pinfunction "2_2") (pintype "passive"))
    )
    (net (code "23") (name "Net-(J2-CC2)") (class "Default")
      (node (ref "J2") (pin "B5") (pinfunction "CC2_B5") (pintype "passive"))
      (node (ref "R5") (pin "2") (pinfunction "2_2") (pintype "passive"))
    )
    (net (code "24") (name "Net-(Q1-D)") (class "Default")
      (node (ref "C20") (pin "2") (pinfunction "2_2") (pintype "passive"))
      (node (ref "D6") (pin "A") (pinfunction "A_A") (pintype "passive"))
      (node (ref "L1") (pin "2") (pinfunction "2_2") (pintype "passive"))
      (node (ref "Q1") (pin "3") (pinfunction "D_3") (pintype "passive"))
    )
    (net (code "25") (name "Net-(Q2-G)") (class "Default")
      (node (ref "Q2") (pin "1") (pinfunction "G_1") (pintype "passive"))
      (node (ref "R2") (pin "2") (pinfunction "2_2") (pintype "passive"))
      (node (ref "R9") (pin "1") (pinfunction "1_1") (pintype "passive"))
    )
    (net (code "26") (name "Net-(Q4-G)") (class "Default")
      (node (ref "Q4") (pin "1") (pinfunction "G_1") (pintype "passive"))
      (node (ref "Q5") (pin "3") (pinfunction "D_3") (pintype "passive"))
      (node (ref "R18") (pin "2") (pinfunction "2_2") (pintype "passive"))
    )
    (net (code "27") (name "Net-(Q7-D)") (class "Default")
      (node (ref "Q7") (pin "3") (pinfunction "D_3") (pintype "passive"))
      (node (ref "Q8") (pin "3") (pinfunction "D_3") (pintype "passive"))
    )
    (net (code "28") (name "Net-(Q7-G)") (class "Default")
      (node (ref "Q7") (pin "1") (pinfunction "G_1") (pintype "passive"))
      (node (ref "U15") (pin "2") (pinfunction "COUT_2") (pintype "bidirectional"))
    )
    (net (code "29") (name "Net-(Q8-G)") (class "Default")
      (node (ref "Q8") (pin "1") (pinfunction "G_1") (pintype "passive"))
      (node (ref "U15") (pin "3") (pinfunction "DOUT_3") (pintype "bidirectional"))
    )
    (net (code "30") (name "Net-(R146-Pad2)") (class "Default")
      (node (ref "R146") (pin "2") (pinfunction "2_2") (pintype "passive"))
      (node (ref "R17") (pin "2") (pinfunction "2_2") (pintype "passive"))
      (node (ref "SJ1") (pin "2") (pinfunction "2_2") (pintype "passive"))
    )
    (net (code "31") (name "Net-(U1-PROG)") (class "Default")
      (node (ref "R16") (pin "2") (pinfunction "2_2") (pintype "passive"))
      (node (ref "U1") (pin "5") (pinfunction "PROG_5") (pintype "passive"))
    )
    (net (code "32") (name "Net-(U2-FB)") (class "Default")
      (node (ref "R10") (pin "2") (pinfunction "2_2") (pintype "passive"))
      (node (ref "R11") (pin "2") (pinfunction "2_2") (pintype "passive"))
      (node (ref "U2") (pin "2") (pinfunction "FB_2") (pintype "passive"))
    )
    (net (code "33") (name "Net-(U3-FB)") (class "Default")
      (node (ref "R12") (pin "2") (pinfunction "2_2") (pintype "passive"))
      (node (ref "R13") (pin "2") (pinfunction "2_2") (pintype "passive"))
      (node (ref "U3") (pin "2") (pinfunction "FB_2") (pintype "passive"))
    )
    (net (code "34") (name "Net-(U5-VDD)") (class "Default")
      (node (ref "C10") (pin "2") (pinfunction "2_2") (pintype "passive"))
      (node (ref "R145") (pin "1") (pinfunction "1_1") (pintype "passive"))
      (node (ref "U5") (pin "1") (pinfunction "VDD_1") (pintype "bidirectional"))
    )
    (net (code "35") (name "Net-(U15-BAT)") (class "Default")
      (node (ref "C77") (pin "1") (pinfunction "1_1") (pintype "passive"))
      (node (ref "R87") (pin "1") (pinfunction "1_1") (pintype "passive"))
      (node (ref "U15") (pin "5") (pinfunction "BAT_5") (pintype "bidirectional"))
    )
    (net (code "36") (name "Net-(U15-V-)") (class "Default")
      (node (ref "R91") (pin "2") (pinfunction "2_2") (pintype "passive"))
      (node (ref "U15") (pin "6") (pinfunction "V-_6") (pintype "bidirectional"))
    )
    (net (code "37") (name "RES#") (class "Default")
      (node (ref "J3") (pin "10") (pinfunction "10_10") (pintype "passive"))
      (node (ref "MOD1") (pin "PA6") (pinfunction "PA6_PA6") (pintype "bidirectional"))
    )
    (net (code "38") (name "RESE") (class "Default")
      (node (ref "J3") (pin "3") (pinfunction "3_3") (pintype "passive"))
      (node (ref "Q1") (pin "2") (pinfunction "S_2") (pintype "passive"))
      (node (ref "R1") (pin "1") (pinfunction "1_1") (pintype "passive"))
      (node (ref "R21") (pin "2") (pinfunction "2_2") (pintype "passive"))
    )
    (net (code "39") (name "SCL_SENS") (class "Default")
      (node (ref "C16") (pin "2") (pinfunction "2_2") (pintype "passive"))
      (node (ref "MOD1") (pin "PA9") (pinfunction "PA9_PA9") (pintype "bidirectional"))
      (node (ref "R17") (pin "1") (pinfunction "1_1") (pintype "passive"))
      (node (ref "U26") (pin "2") (pinfunction "SCL_2") (pintype "bidirectional"))
      (node (ref "U5") (pin "6") (pinfunction "SCL_6") (pintype "bidirectional"))
    )
    (net (code "40") (name "SDA_SENS") (class "Default")
      (node (ref "C128") (pin "2") (pinfunction "2_2") (pintype "passive"))
      (node (ref "MOD1") (pin "PA10") (pinfunction "PA10_PA10") (pintype "bidirectional"))
      (node (ref "R146") (pin "1") (pinfunction "1_1") (pintype "passive"))
      (node (ref "U26") (pin "1") (pinfunction "SDA_1") (pintype "bidirectional"))
      (node (ref "U5") (pin "3") (pinfunction "SDA_3") (pintype "bidirectional"))
    )
    (net (code "41") (name "SENSE_EN") (class "Default")
      (node (ref "MOD1") (pin "PA1") (pinfunction "PA1_PA1") (pintype "bidirectional"))
      (node (ref "R14") (pin "2") (pinfunction "2_2") (pintype "passive"))
      (node (ref "U3") (pin "4") (pinfunction "EN_4") (pintype "input"))
    )
    (net (code "42") (name "SPI_CLK") (class "Default")
      (node (ref "J3") (pin "13") (pinfunction "13_13") (pintype "passive"))
      (node (ref "MOD1") (pin "PA5") (pinfunction "PA5_PA5") (pintype "bidirectional"))
    )
    (net (code "43") (name "SPI_MISO") (class "Default")
      (node (ref "MOD1") (pin "PA11") (pinfunction "PA11_PA11") (pintype "bidirectional"))
    )
    (net (code "44") (name "SPI_MOSI") (class "Default")
      (node (ref "J3") (pin "14") (pinfunction "14_14") (pintype "passive"))
      (node (ref "MOD1") (pin "PA7") (pinfunction "PA7_PA7") (pintype "bidirectional"))
    )
    (net (code "45") (name "SUPPLY") (class "Default")
      (node (ref "C1") (pin "1") (pinfunction "1_1") (pintype "passive"))
      (node (ref "C11") (pin "1") (pinfunction "1_1") (pintype "passive"))
      (node (ref "C5") (pin "1") (pinfunction "1_1") (pintype "passive"))
      (node (ref "C7") (pin "1") (pinfunction "1_1") (pintype "passive"))
      (node (ref "Q3") (pin "2") (pinfunction "S_2") (pintype "passive"))
      (node (ref "Q4") (pin "2") (pinfunction "S_2") (pintype "passive"))
      (node (ref "R14") (pin "1") (pinfunction "1_1") (pintype "passive"))
      (node (ref "R18") (pin "1") (pinfunction "1_1") (pintype "passive"))
      (node (ref "TP5") (pin "TP") (pinfunction "TP_TP") (pintype "input"))
      (node (ref "U2") (pin "4") (pinfunction "EN_4") (pintype "input"))
      (node (ref "U2") (pin "6") (pinfunction "IN_6") (pintype "power_in"))
      (node (ref "U3") (pin "6") (pinfunction "IN_6") (pintype "power_in"))
    )
    (net (code "46") (name "SWCLK") (class "Default")
      (node (ref "CN1") (pin "4") (pinfunction "SWCLK_4") (pintype "bidirectional"))
      (node (ref "MOD1") (pin "SWCLK") (pinfunction "SWCLK_SWCLK") (pintype "bidirectional"))
    )
    (net (code "47") (name "SWDIO") (class "Default")
      (node (ref "CN1") (pin "2") (pinfunction "SWDIO_2") (pintype "bidirectional"))
      (node (ref "MOD1") (pin "SWDIO") (pinfunction "SWDIO_SWDIO") (pintype "bidirectional"))
    )
    (net (code "48") (name "SWO") (class "Default")
      (node (ref "CN1") (pin "6") (pinfunction "SWO_6") (pintype "bidirectional"))
    )
    (net (code "49") (name "TSCL") (class "Default")
      (node (ref "J3") (pin "6") (pinfunction "6_6") (pintype "passive"))
    )
    (net (code "50") (name "TSDA") (class "Default")
      (node (ref "J3") (pin "7") (pinfunction "7_7") (pintype "passive"))
    )
    (net (code "51") (name "USART_RX") (class "Default")
      (node (ref "CN2") (pin "3") (pinfunction "3_3") (pintype "bidirectional"))
      (node (ref "MOD1") (pin "PB7") (pinfunction "PB7_PB7") (pintype "bidirectional"))
    )
    (net (code "52") (name "USART_TX") (class "Default")
      (node (ref "CN2") (pin "2") (pinfunction "2_2") (pintype "bidirectional"))
      (node (ref "MOD1") (pin "PB6") (pinfunction "PB6_PB6") (pintype "bidirectional"))
    )
    (net (code "53") (name "USER_BUTTON") (class "Default")
      (node (ref "C18") (pin "1") (pinfunction "1_1") (pintype "passive"))
      (node (ref "MOD1") (pin "PA4") (pinfunction "PA4_PA4") (pintype "bidirectional"))
      (node (ref "R20") (pin "2") (pinfunction "2_2") (pintype "passive"))
      (node (ref "SW2") (pin "2_1") (pinfunction "2_2_1") (pintype "passive"))
      (node (ref "SW2") (pin "2_2") (pinfunction "2_2_2") (pintype "passive"))
    )
    (net (code "54") (name "VCOM") (class "Default")
      (node (ref "C19") (pin "1") (pinfunction "1_1") (pintype "passive"))
      (node (ref "J3") (pin "24") (pinfunction "24_24") (pintype "passive"))
    )
    (net (code "55") (name "VDD") (class "Default")
      (node (ref "C25") (pin "1") (pinfunction "1_1") (pintype "passive"))
      (node (ref "J3") (pin "18") (pinfunction "18_18") (pintype "passive"))
    )
    (net (code "56") (name "VGH") (class "Default")
      (node (ref "C21") (pin "1") (pinfunction "1_1") (pintype "passive"))
      (node (ref "D6") (pin "K") (pinfunction "K_K") (pintype "passive"))
      (node (ref "J3") (pin "21") (pinfunction "21_21") (pintype "passive"))
    )
    (net (code "57") (name "VGL") (class "Default")
      (node (ref "C28") (pin "1") (pinfunction "1_1") (pintype "passive"))
      (node (ref "D3") (pin "A") (pinfunction "A_A") (pintype "passive"))
      (node (ref "J3") (pin "23") (pinfunction "23_23") (pintype "passive"))
    )
    (net (code "58") (name "VSH1") (class "Default")
      (node (ref "C26") (pin "1") (pinfunction "1_1") (pintype "passive"))
      (node (ref "J3") (pin "20") (pinfunction "20_20") (pintype "passive"))
    )
    (net (code "59") (name "VSH2") (class "Default")
      (node (ref "C23") (pin "1") (pinfunction "1_1") (pintype "passive"))
      (node (ref "J3") (pin "5") (pinfunction "5_5") (pintype "passive"))
    )
    (net (code "60") (name "VSL") (class "Default")
      (node (ref "C27") (pin "1") (pinfunction "1_1") (pintype "passive"))
      (node (ref "J3") (pin "22") (pinfunction "22_22") (pintype "passive"))
    )
    (net (code "61") (name "unconnected-(J2-DN1-PadA7)") (class "Default")
      (node (ref "J2") (pin "A7") (pinfunction "DN1_A7") (pintype "passive"))
    )
    (net (code "62") (name "unconnected-(J2-DN2-PadB7)") (class "Default")
      (node (ref "J2") (pin "B7") (pinfunction "DN2_B7") (pintype "passive"))
    )
    (net (code "63") (name "unconnected-(J2-DP1-PadA6)") (class "Default")
      (node (ref "J2") (pin "A6") (pinfunction "DP1_A6") (pintype "passive"))
    )
    (net (code "64") (name "unconnected-(J2-DP2-PadB6)") (class "Default")
      (node (ref "J2") (pin "B6") (pinfunction "DP2_B6") (pintype "passive"))
    )
    (net (code "65") (name "unconnected-(J2-SBU1-PadA8)") (class "Default")
      (node (ref "J2") (pin "A8") (pinfunction "SBU1_A8") (pintype "passive"))
    )
    (net (code "66") (name "unconnected-(J2-SBU2-PadB8)") (class "Default")
      (node (ref "J2") (pin "B8") (pinfunction "SBU2_B8") (pintype "passive"))
    )
    (net (code "67") (name "unconnected-(J3-Pad1)") (class "Default")
      (node (ref "J3") (pin "1") (pinfunction "1_1") (pintype "passive"))
    )
    (net (code "68") (name "unconnected-(J3-Pad4)") (class "Default")
      (node (ref "J3") (pin "4") (pinfunction "4_4") (pintype "passive"))
    )
    (net (code "69") (name "unconnected-(J3-Pad19)") (class "Default")
      (node (ref "J3") (pin "19") (pinfunction "19_19") (pintype "passive"))
    )
    (net (code "70") (name "unconnected-(MOD1-PadPA0)") (class "Default")
      (node (ref "MOD1") (pin "PA0") (pinfunction "PA0_PA0") (pintype "bidirectional"))
    )
    (net (code "71") (name "unconnected-(MOD1-PadPA8)") (class "Default")
      (node (ref "MOD1") (pin "PA8") (pinfunction "PA8_PA8") (pintype "bidirectional"))
    )
    (net (code "72") (name "unconnected-(MOD1-PadPB4)") (class "Default")
      (node (ref "MOD1") (pin "PB4") (pinfunction "PB4_PB4") (pintype "bidirectional"))
    )
  )
)
